# main3.net
KiCad netlist of a schematic drawn in EAGLE
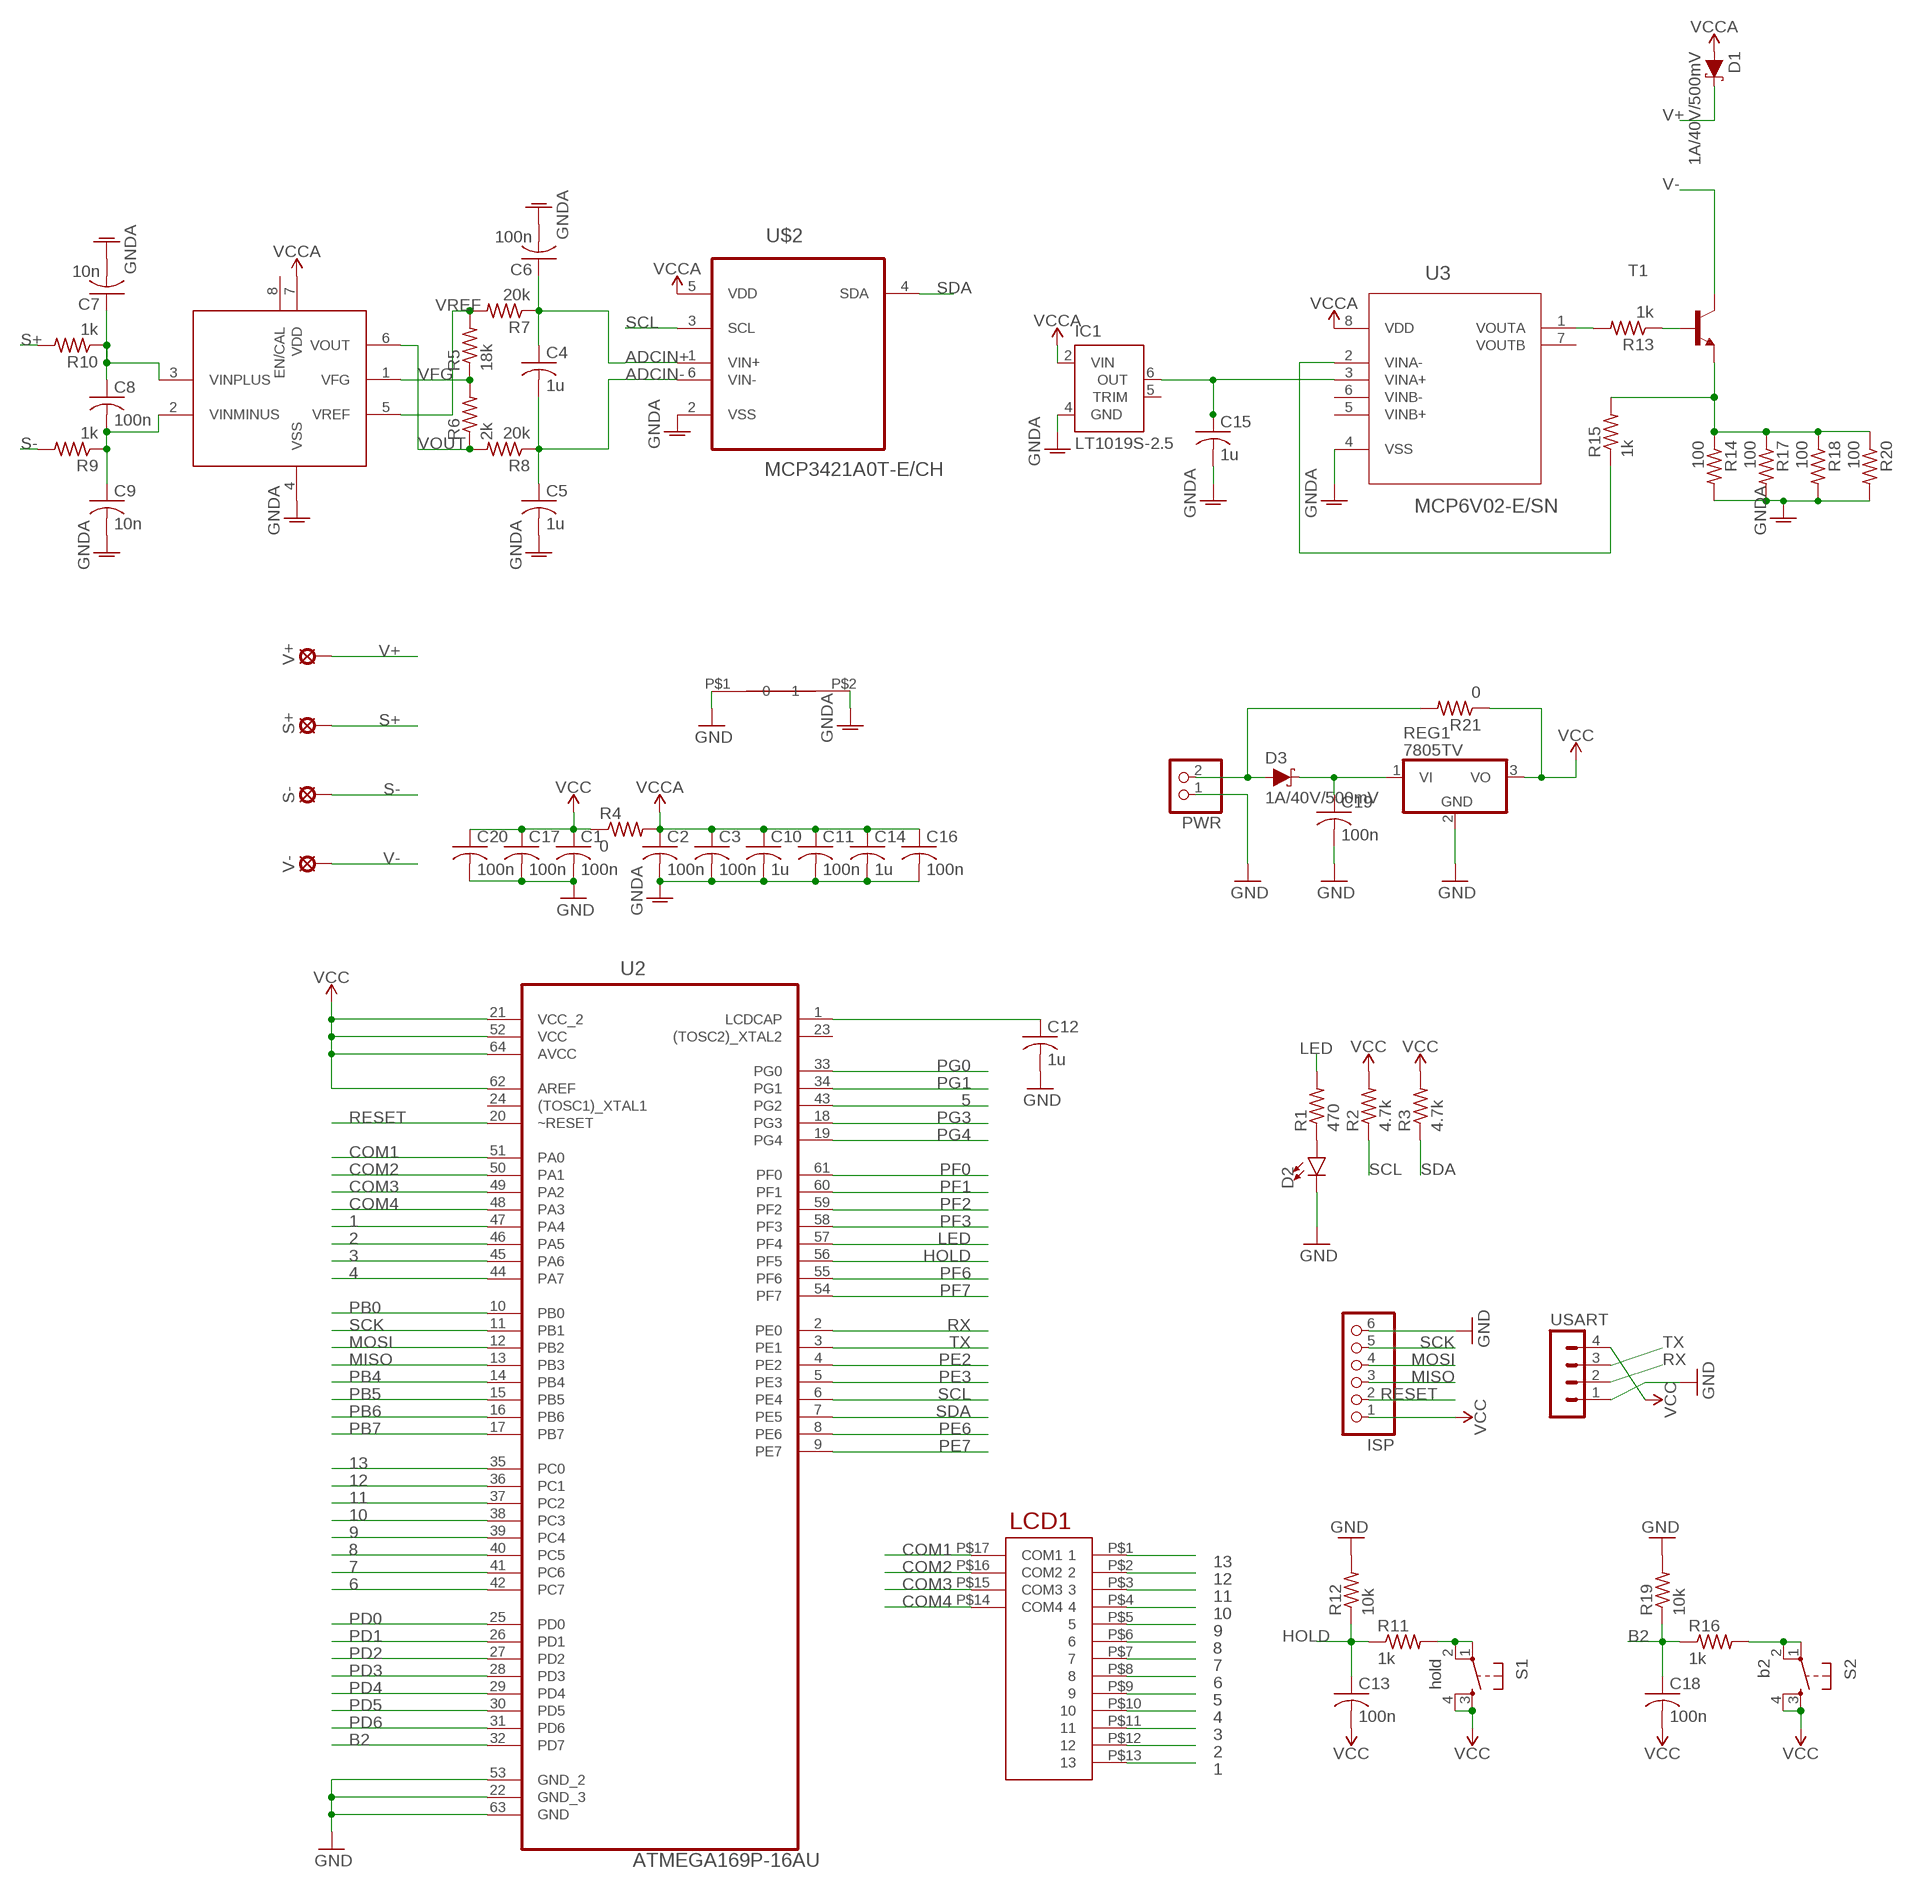
[diagram p0: schematic, sheet 1]

(export (version "E")
  (design (tool "Eeschema 10.0.6"))
  (components
    (comp (ref "C1")
      (value "100n")
      (footprint "eagle-import:C0603")
      (libsource (lib "eagle-import") (part "C-USC0603"))
    )
    (comp (ref "C2")
      (value "100n")
      (footprint "eagle-import:C0603")
      (libsource (lib "eagle-import") (part "C-USC0603"))
    )
    (comp (ref "C3")
      (value "100n")
      (footprint "eagle-import:C0603")
      (libsource (lib "eagle-import") (part "C-USC0603"))
    )
    (comp (ref "C4")
      (value "1u")
      (footprint "eagle-import:C0603")
      (libsource (lib "eagle-import") (part "C-USC0603"))
    )
    (comp (ref "C5")
      (value "1u")
      (footprint "eagle-import:C0603")
      (libsource (lib "eagle-import") (part "C-USC0603"))
    )
    (comp (ref "C6")
      (value "100n")
      (footprint "eagle-import:C0603")
      (libsource (lib "eagle-import") (part "C-USC0603"))
    )
    (comp (ref "C7")
      (value "10n")
      (footprint "eagle-import:C0603")
      (libsource (lib "eagle-import") (part "C-USC0603"))
    )
    (comp (ref "C8")
      (value "100n")
      (footprint "eagle-import:C0603")
      (libsource (lib "eagle-import") (part "C-USC0603"))
    )
    (comp (ref "C9")
      (value "10n")
      (footprint "eagle-import:C0603")
      (libsource (lib "eagle-import") (part "C-USC0603"))
    )
    (comp (ref "C10")
      (value "1u")
      (footprint "eagle-import:C0603")
      (libsource (lib "eagle-import") (part "C-USC0603"))
    )
    (comp (ref "C11")
      (value "100n")
      (footprint "eagle-import:C0603")
      (libsource (lib "eagle-import") (part "C-USC0603"))
    )
    (comp (ref "C12")
      (value "1u")
      (footprint "eagle-import:C0603")
      (libsource (lib "eagle-import") (part "C-USC0603"))
    )
    (comp (ref "C13")
      (value "100n")
      (footprint "eagle-import:C0603")
      (libsource (lib "eagle-import") (part "C-USC0603"))
    )
    (comp (ref "C14")
      (value "1u")
      (footprint "eagle-import:C0603")
      (libsource (lib "eagle-import") (part "C-USC0603"))
    )
    (comp (ref "C15")
      (value "1u")
      (footprint "eagle-import:C0603")
      (libsource (lib "eagle-import") (part "C-USC0603"))
    )
    (comp (ref "C16")
      (value "100n")
      (footprint "eagle-import:C0603")
      (libsource (lib "eagle-import") (part "C-USC0603"))
    )
    (comp (ref "C17")
      (value "100n")
      (footprint "eagle-import:C0603")
      (libsource (lib "eagle-import") (part "C-USC0603"))
    )
    (comp (ref "C18")
      (value "100n")
      (footprint "eagle-import:C0603")
      (libsource (lib "eagle-import") (part "C-USC0603"))
    )
    (comp (ref "C19")
      (value "100n")
      (footprint "eagle-import:C0603")
      (libsource (lib "eagle-import") (part "C-USC0603"))
    )
    (comp (ref "C20")
      (value "100n")
      (footprint "eagle-import:C0603")
      (libsource (lib "eagle-import") (part "C-USC0603"))
    )
    (comp (ref "D1")
      (value "1A/40V/500mV")
      (footprint "eagle-import:SMA-DIODE")
      (libsource (lib "eagle-import") (part "DIODE-SCHOTTKY-SS14"))
    )
    (comp (ref "D2")
      (value "LED5MM")
      (footprint "eagle-import:LED_5MM")
      (libsource (lib "eagle-import") (part "LED5MM"))
    )
    (comp (ref "D3")
      (value "1A/40V/500mV")
      (footprint "eagle-import:SMA-DIODE")
      (libsource (lib "eagle-import") (part "DIODE-SCHOTTKY-SS14"))
    )
    (comp (ref "IC1")
      (value "LT1019S-2.5")
      (footprint "eagle-import:SOIC8")
      (fields (field (name "MPN") "LT1019CS8-2.5#PBF"))
      (libsource (lib "eagle-import") (part "LT1019?S-2.5"))
    )
    (comp (ref "ISP")
      (value "PINHD-1X6")
      (footprint "eagle-import:1X06")
      (libsource (lib "eagle-import") (part "PINHD-1X6"))
    )
    (comp (ref "LCD1")
      (value "GDC0570_LCD")
      (footprint "eagle-import:GDC0570_LCD")
      (libsource (lib "eagle-import") (part "GDC0570_LCD"))
    )
    (comp (ref "PWR")
      (value "PINHD-1X2")
      (footprint "eagle-import:1X02")
      (libsource (lib "eagle-import") (part "PINHD-1X2"))
    )
    (comp (ref "R1")
      (value "470")
      (footprint "eagle-import:R0603")
      (libsource (lib "eagle-import") (part "R-US_R0603"))
    )
    (comp (ref "R2")
      (value "4.7k")
      (footprint "eagle-import:R0603")
      (libsource (lib "eagle-import") (part "R-US_R0603"))
    )
    (comp (ref "R3")
      (value "4.7k")
      (footprint "eagle-import:R0603")
      (libsource (lib "eagle-import") (part "R-US_R0603"))
    )
    (comp (ref "R4")
      (value "0")
      (footprint "eagle-import:0309_12")
      (libsource (lib "eagle-import") (part "R-US_0309/12"))
    )
    (comp (ref "R5")
      (value "18k")
      (footprint "eagle-import:R0603")
      (libsource (lib "eagle-import") (part "R-US_R0603"))
    )
    (comp (ref "R6")
      (value "2k")
      (footprint "eagle-import:R0603")
      (libsource (lib "eagle-import") (part "R-US_R0603"))
    )
    (comp (ref "R7")
      (value "20k")
      (footprint "eagle-import:R0603")
      (libsource (lib "eagle-import") (part "R-US_R0603"))
    )
    (comp (ref "R8")
      (value "20k")
      (footprint "eagle-import:R0603")
      (libsource (lib "eagle-import") (part "R-US_R0603"))
    )
    (comp (ref "R9")
      (value "1k")
      (footprint "eagle-import:R0603")
      (libsource (lib "eagle-import") (part "R-US_R0603"))
    )
    (comp (ref "R10")
      (value "1k")
      (footprint "eagle-import:R0603")
      (libsource (lib "eagle-import") (part "R-US_R0603"))
    )
    (comp (ref "R11")
      (value "1k")
      (footprint "eagle-import:R0603")
      (libsource (lib "eagle-import") (part "R-US_R0603"))
    )
    (comp (ref "R12")
      (value "10k")
      (footprint "eagle-import:R0603")
      (libsource (lib "eagle-import") (part "R-US_R0603"))
    )
    (comp (ref "R13")
      (value "1k")
      (footprint "eagle-import:R0603")
      (libsource (lib "eagle-import") (part "R-US_R0603"))
    )
    (comp (ref "R14")
      (value "100")
      (footprint "eagle-import:R0603")
      (libsource (lib "eagle-import") (part "R-US_R0603"))
    )
    (comp (ref "R15")
      (value "1k")
      (footprint "eagle-import:R0603")
      (libsource (lib "eagle-import") (part "R-US_R0603"))
    )
    (comp (ref "R16")
      (value "1k")
      (footprint "eagle-import:R0603")
      (libsource (lib "eagle-import") (part "R-US_R0603"))
    )
    (comp (ref "R17")
      (value "100")
      (footprint "eagle-import:R0603")
      (libsource (lib "eagle-import") (part "R-US_R0603"))
    )
    (comp (ref "R18")
      (value "100")
      (footprint "eagle-import:R0603")
      (libsource (lib "eagle-import") (part "R-US_R0603"))
    )
    (comp (ref "R19")
      (value "10k")
      (footprint "eagle-import:R0603")
      (libsource (lib "eagle-import") (part "R-US_R0603"))
    )
    (comp (ref "R20")
      (value "100")
      (footprint "eagle-import:R0603")
      (libsource (lib "eagle-import") (part "R-US_R0603"))
    )
    (comp (ref "R21")
      (value "0")
      (footprint "eagle-import:R0603")
      (libsource (lib "eagle-import") (part "R-US_R0603"))
    )
    (comp (ref "REG1")
      (value "7805TV")
      (footprint "eagle-import:TO220V")
      (libsource (lib "eagle-import") (part "78TV05"))
    )
    (comp (ref "S+")
      (value "MCS08")
      (footprint "eagle-import:MCS08")
      (libsource (lib "eagle-import") (part "MCS08"))
    )
    (comp (ref "S-")
      (value "MCS08")
      (footprint "eagle-import:MCS08")
      (libsource (lib "eagle-import") (part "MCS08"))
    )
    (comp (ref "S1")
      (value "hold")
      (footprint "eagle-import:TACTILE-PTH")
      (libsource (lib "eagle-import") (part "TAC_SWITCHPTH"))
    )
    (comp (ref "S2")
      (value "b2")
      (footprint "eagle-import:TACTILE-PTH")
      (libsource (lib "eagle-import") (part "TAC_SWITCHPTH"))
    )
    (comp (ref "T1")
      (value "MMBT3904LT1-NPN-SOT23-BEC")
      (footprint "eagle-import:SOT23-BEC")
      (libsource (lib "eagle-import") (part "-NPN-SOT23-BECMMBT3904LT1"))
    )
    (comp (ref "U$2")
      (value "MCP3421A0T-E/CH")
      (footprint "eagle-import:SOT95P270X145-6N")
      (libsource (lib "eagle-import") (part "MCP3421A0T-E/CH"))
    )
    (comp (ref "U$3")
      (value "MCP6N11")
      (footprint "eagle-import:SOIC8")
      (libsource (lib "eagle-import") (part "MCP6N11"))
    )
    (comp (ref "U$10")
      (value "SHORT32")
      (footprint "eagle-import:SHORT_32")
      (libsource (lib "eagle-import") (part "SHORT32"))
    )
    (comp (ref "U2")
      (value "ATMEGA169P-16AU")
      (footprint "eagle-import:QFP80P1600X1600X120-64N")
      (libsource (lib "eagle-import") (part "ATMEGA169P-16AU"))
    )
    (comp (ref "U3")
      (value "MCP6V02-E/SN")
      (footprint "eagle-import:SOIC127P600X175-8N")
      (libsource (lib "eagle-import") (part "MCP6V02-E/SN"))
    )
    (comp (ref "USART")
      (value "MA04-1")
      (footprint "eagle-import:MA04-1")
      (libsource (lib "eagle-import") (part "MA04-1"))
    )
    (comp (ref "V+")
      (value "MCS08")
      (footprint "eagle-import:MCS08")
      (libsource (lib "eagle-import") (part "MCS08"))
    )
    (comp (ref "V-")
      (value "MCS08")
      (footprint "eagle-import:MCS08")
      (libsource (lib "eagle-import") (part "MCS08"))
    )
  )
  (nets
    (net (code "1") (name "/1") (class "Default")
      (node (ref "LCD1") (pin "P$13") (pinfunction "13_P$13") (pintype "bidirectional"))
      (node (ref "U2") (pin "47") (pinfunction "PA4_47") (pintype "bidirectional"))
    )
    (net (code "2") (name "/2") (class "Default")
      (node (ref "LCD1") (pin "P$12") (pinfunction "12_P$12") (pintype "bidirectional"))
      (node (ref "U2") (pin "46") (pinfunction "PA5_46") (pintype "bidirectional"))
    )
    (net (code "3") (name "/3") (class "Default")
      (node (ref "LCD1") (pin "P$11") (pinfunction "11_P$11") (pintype "bidirectional"))
      (node (ref "U2") (pin "45") (pinfunction "PA6_45") (pintype "bidirectional"))
    )
    (net (code "4") (name "/4") (class "Default")
      (node (ref "LCD1") (pin "P$10") (pinfunction "10_P$10") (pintype "bidirectional"))
      (node (ref "U2") (pin "44") (pinfunction "PA7_44") (pintype "bidirectional"))
    )
    (net (code "5") (name "/5") (class "Default")
      (node (ref "LCD1") (pin "P$9") (pinfunction "9_P$9") (pintype "bidirectional"))
      (node (ref "U2") (pin "43") (pinfunction "PG2_43") (pintype "bidirectional"))
    )
    (net (code "6") (name "/6") (class "Default")
      (node (ref "LCD1") (pin "P$8") (pinfunction "8_P$8") (pintype "bidirectional"))
      (node (ref "U2") (pin "42") (pinfunction "PC7_42") (pintype "bidirectional"))
    )
    (net (code "7") (name "/7") (class "Default")
      (node (ref "LCD1") (pin "P$7") (pinfunction "7_P$7") (pintype "bidirectional"))
      (node (ref "U2") (pin "41") (pinfunction "PC6_41") (pintype "bidirectional"))
    )
    (net (code "8") (name "/8") (class "Default")
      (node (ref "LCD1") (pin "P$6") (pinfunction "6_P$6") (pintype "bidirectional"))
      (node (ref "U2") (pin "40") (pinfunction "PC5_40") (pintype "bidirectional"))
    )
    (net (code "9") (name "/9") (class "Default")
      (node (ref "LCD1") (pin "P$5") (pinfunction "5_P$5") (pintype "bidirectional"))
      (node (ref "U2") (pin "39") (pinfunction "PC4_39") (pintype "bidirectional"))
    )
    (net (code "10") (name "/10") (class "Default")
      (node (ref "LCD1") (pin "P$4") (pinfunction "4_P$4") (pintype "bidirectional"))
      (node (ref "U2") (pin "38") (pinfunction "PC3_38") (pintype "bidirectional"))
    )
    (net (code "11") (name "/11") (class "Default")
      (node (ref "LCD1") (pin "P$3") (pinfunction "3_P$3") (pintype "bidirectional"))
      (node (ref "U2") (pin "37") (pinfunction "PC2_37") (pintype "bidirectional"))
    )
    (net (code "12") (name "/12") (class "Default")
      (node (ref "LCD1") (pin "P$2") (pinfunction "2_P$2") (pintype "bidirectional"))
      (node (ref "U2") (pin "36") (pinfunction "PC1_36") (pintype "bidirectional"))
    )
    (net (code "13") (name "/13") (class "Default")
      (node (ref "LCD1") (pin "P$1") (pinfunction "1_P$1") (pintype "bidirectional"))
      (node (ref "U2") (pin "35") (pinfunction "PC0_35") (pintype "bidirectional"))
    )
    (net (code "14") (name "/ADCIN+") (class "Default")
      (node (ref "C4") (pin "1") (pinfunction "1_1") (pintype "passive"))
      (node (ref "C6") (pin "1") (pinfunction "1_1") (pintype "passive"))
      (node (ref "R7") (pin "1") (pinfunction "1_1") (pintype "passive"))
      (node (ref "U$2") (pin "1") (pinfunction "VIN+_1") (pintype "input"))
    )
    (net (code "15") (name "/ADCIN-") (class "Default")
      (node (ref "C4") (pin "2") (pinfunction "2_2") (pintype "passive"))
      (node (ref "C5") (pin "1") (pinfunction "1_1") (pintype "passive"))
      (node (ref "R8") (pin "1") (pinfunction "1_1") (pintype "passive"))
      (node (ref "U$2") (pin "6") (pinfunction "VIN-_6") (pintype "input"))
    )
    (net (code "16") (name "/B2") (class "Default")
      (node (ref "C18") (pin "1") (pinfunction "1_1") (pintype "passive"))
      (node (ref "R16") (pin "1") (pinfunction "1_1") (pintype "passive"))
      (node (ref "R19") (pin "1") (pinfunction "1_1") (pintype "passive"))
      (node (ref "U2") (pin "32") (pinfunction "PD7_32") (pintype "bidirectional"))
    )
    (net (code "17") (name "/COM1") (class "Default")
      (node (ref "LCD1") (pin "P$17") (pinfunction "COM1_P$17") (pintype "bidirectional"))
      (node (ref "U2") (pin "51") (pinfunction "PA0_51") (pintype "bidirectional"))
    )
    (net (code "18") (name "/COM2") (class "Default")
      (node (ref "LCD1") (pin "P$16") (pinfunction "COM2_P$16") (pintype "bidirectional"))
      (node (ref "U2") (pin "50") (pinfunction "PA1_50") (pintype "bidirectional"))
    )
    (net (code "19") (name "/COM3") (class "Default")
      (node (ref "LCD1") (pin "P$15") (pinfunction "COM3_P$15") (pintype "bidirectional"))
      (node (ref "U2") (pin "49") (pinfunction "PA2_49") (pintype "bidirectional"))
    )
    (net (code "20") (name "/COM4") (class "Default")
      (node (ref "LCD1") (pin "P$14") (pinfunction "COM4_P$14") (pintype "bidirectional"))
      (node (ref "U2") (pin "48") (pinfunction "PA3_48") (pintype "bidirectional"))
    )
    (net (code "21") (name "/HOLD") (class "Default")
      (node (ref "C13") (pin "1") (pinfunction "1_1") (pintype "passive"))
      (node (ref "R11") (pin "1") (pinfunction "1_1") (pintype "passive"))
      (node (ref "R12") (pin "1") (pinfunction "1_1") (pintype "passive"))
      (node (ref "U2") (pin "56") (pinfunction "PF5_56") (pintype "bidirectional"))
    )
    (net (code "22") (name "/LED") (class "Default")
      (node (ref "R1") (pin "2") (pinfunction "2_2") (pintype "passive"))
      (node (ref "U2") (pin "57") (pinfunction "PF4_57") (pintype "bidirectional"))
    )
    (net (code "23") (name "/MISO") (class "Default")
      (node (ref "ISP") (pin "3") (pinfunction "3_3") (pintype "passive"))
      (node (ref "U2") (pin "13") (pinfunction "PB3_13") (pintype "bidirectional"))
    )
    (net (code "24") (name "/MOSI") (class "Default")
      (node (ref "ISP") (pin "4") (pinfunction "4_4") (pintype "passive"))
      (node (ref "U2") (pin "12") (pinfunction "PB2_12") (pintype "bidirectional"))
    )
    (net (code "25") (name "/PB0") (class "Default")
      (node (ref "U2") (pin "10") (pinfunction "PB0_10") (pintype "bidirectional"))
    )
    (net (code "26") (name "/PB4") (class "Default")
      (node (ref "U2") (pin "14") (pinfunction "PB4_14") (pintype "bidirectional"))
    )
    (net (code "27") (name "/PB5") (class "Default")
      (node (ref "U2") (pin "15") (pinfunction "PB5_15") (pintype "bidirectional"))
    )
    (net (code "28") (name "/PB6") (class "Default")
      (node (ref "U2") (pin "16") (pinfunction "PB6_16") (pintype "bidirectional"))
    )
    (net (code "29") (name "/PB7") (class "Default")
      (node (ref "U2") (pin "17") (pinfunction "PB7_17") (pintype "bidirectional"))
    )
    (net (code "30") (name "/PD0") (class "Default")
      (node (ref "U2") (pin "25") (pinfunction "PD0_25") (pintype "bidirectional"))
    )
    (net (code "31") (name "/PD1") (class "Default")
      (node (ref "U2") (pin "26") (pinfunction "PD1_26") (pintype "bidirectional"))
    )
    (net (code "32") (name "/PD2") (class "Default")
      (node (ref "U2") (pin "27") (pinfunction "PD2_27") (pintype "bidirectional"))
    )
    (net (code "33") (name "/PD3") (class "Default")
      (node (ref "U2") (pin "28") (pinfunction "PD3_28") (pintype "bidirectional"))
    )
    (net (code "34") (name "/PD4") (class "Default")
      (node (ref "U2") (pin "29") (pinfunction "PD4_29") (pintype "bidirectional"))
    )
    (net (code "35") (name "/PD5") (class "Default")
      (node (ref "U2") (pin "30") (pinfunction "PD5_30") (pintype "bidirectional"))
    )
    (net (code "36") (name "/PD6") (class "Default")
      (node (ref "U2") (pin "31") (pinfunction "PD6_31") (pintype "bidirectional"))
    )
    (net (code "37") (name "/PE2") (class "Default")
      (node (ref "U2") (pin "4") (pinfunction "PE2_4") (pintype "bidirectional"))
    )
    (net (code "38") (name "/PE3") (class "Default")
      (node (ref "U2") (pin "5") (pinfunction "PE3_5") (pintype "bidirectional"))
    )
    (net (code "39") (name "/PE6") (class "Default")
      (node (ref "U2") (pin "8") (pinfunction "PE6_8") (pintype "bidirectional"))
    )
    (net (code "40") (name "/PE7") (class "Default")
      (node (ref "U2") (pin "9") (pinfunction "PE7_9") (pintype "bidirectional"))
    )
    (net (code "41") (name "/PF0") (class "Default")
      (node (ref "U2") (pin "61") (pinfunction "PF0_61") (pintype "bidirectional"))
    )
    (net (code "42") (name "/PF1") (class "Default")
      (node (ref "U2") (pin "60") (pinfunction "PF1_60") (pintype "bidirectional"))
    )
    (net (code "43") (name "/PF2") (class "Default")
      (node (ref "U2") (pin "59") (pinfunction "PF2_59") (pintype "bidirectional"))
    )
    (net (code "44") (name "/PF3") (class "Default")
      (node (ref "U2") (pin "58") (pinfunction "PF3_58") (pintype "bidirectional"))
    )
    (net (code "45") (name "/PF6") (class "Default")
      (node (ref "U2") (pin "55") (pinfunction "PF6_55") (pintype "bidirectional"))
    )
    (net (code "46") (name "/PF7") (class "Default")
      (node (ref "U2") (pin "54") (pinfunction "PF7_54") (pintype "bidirectional"))
    )
    (net (code "47") (name "/PG0") (class "Default")
      (node (ref "U2") (pin "33") (pinfunction "PG0_33") (pintype "bidirectional"))
    )
    (net (code "48") (name "/PG1") (class "Default")
      (node (ref "U2") (pin "34") (pinfunction "PG1_34") (pintype "bidirectional"))
    )
    (net (code "49") (name "/PG3") (class "Default")
      (node (ref "U2") (pin "18") (pinfunction "PG3_18") (pintype "bidirectional"))
    )
    (net (code "50") (name "/PG4") (class "Default")
      (node (ref "U2") (pin "19") (pinfunction "PG4_19") (pintype "bidirectional"))
    )
    (net (code "51") (name "/RESET") (class "Default")
      (node (ref "ISP") (pin "2") (pinfunction "2_2") (pintype "passive"))
      (node (ref "U2") (pin "20") (pinfunction "~{RESET}_20") (pintype "input"))
    )
    (net (code "52") (name "/RX") (class "Default")
      (node (ref "U2") (pin "2") (pinfunction "PE0_2") (pintype "bidirectional"))
      (node (ref "USART") (pin "2") (pinfunction "2_2") (pintype "passive"))
    )
    (net (code "53") (name "/S+") (class "Default")
      (node (ref "R10") (pin "2") (pinfunction "2_2") (pintype "passive"))
      (node (ref "S+") (pin "MP") (pinfunction "MP_MP") (pintype "passive"))
    )
    (net (code "54") (name "/S-") (class "Default")
      (node (ref "R9") (pin "2") (pinfunction "2_2") (pintype "passive"))
      (node (ref "S-") (pin "MP") (pinfunction "MP_MP") (pintype "passive"))
    )
    (net (code "55") (name "/SCK") (class "Default")
      (node (ref "ISP") (pin "5") (pinfunction "5_5") (pintype "passive"))
      (node (ref "U2") (pin "11") (pinfunction "PB1_11") (pintype "bidirectional"))
    )
    (net (code "56") (name "/SCL") (class "Default")
      (node (ref "R2") (pin "1") (pinfunction "1_1") (pintype "passive"))
      (node (ref "U$2") (pin "3") (pinfunction "SCL_3") (pintype "input"))
      (node (ref "U2") (pin "6") (pinfunction "PE4_6") (pintype "bidirectional"))
    )
    (net (code "57") (name "/SDA") (class "Default")
      (node (ref "R3") (pin "1") (pinfunction "1_1") (pintype "passive"))
      (node (ref "U$2") (pin "4") (pinfunction "SDA_4") (pintype "bidirectional"))
      (node (ref "U2") (pin "7") (pinfunction "PE5_7") (pintype "bidirectional"))
    )
    (net (code "58") (name "/TX") (class "Default")
      (node (ref "U2") (pin "3") (pinfunction "PE1_3") (pintype "bidirectional"))
      (node (ref "USART") (pin "3") (pinfunction "3_3") (pintype "passive"))
    )
    (net (code "59") (name "/V+") (class "Default")
      (node (ref "D1") (pin "C") (pinfunction "C_C") (pintype "passive"))
      (node (ref "V+") (pin "MP") (pinfunction "MP_MP") (pintype "passive"))
    )
    (net (code "60") (name "/V-") (class "Default")
      (node (ref "T1") (pin "C") (pinfunction "C_C") (pintype "passive"))
      (node (ref "V-") (pin "MP") (pinfunction "MP_MP") (pintype "passive"))
    )
    (net (code "61") (name "/VFG") (class "Default")
      (node (ref "R5") (pin "1") (pinfunction "1_1") (pintype "passive"))
      (node (ref "R6") (pin "2") (pinfunction "2_2") (pintype "passive"))
      (node (ref "U$3") (pin "1") (pinfunction "VFG_1") (pintype "bidirectional"))
    )
    (net (code "62") (name "/VOUT") (class "Default")
      (node (ref "R6") (pin "1") (pinfunction "1_1") (pintype "passive"))
      (node (ref "R8") (pin "2") (pinfunction "2_2") (pintype "passive"))
      (node (ref "U$3") (pin "6") (pinfunction "VOUT_6") (pintype "bidirectional"))
    )
    (net (code "63") (name "/VREF") (class "Default")
      (node (ref "R5") (pin "2") (pinfunction "2_2") (pintype "passive"))
      (node (ref "R7") (pin "2") (pinfunction "2_2") (pintype "passive"))
      (node (ref "U$3") (pin "5") (pinfunction "VREF_5") (pintype "bidirectional"))
    )
    (net (code "64") (name "GND") (class "Default")
      (node (ref "C1") (pin "2") (pinfunction "2_2") (pintype "passive"))
      (node (ref "C12") (pin "2") (pinfunction "2_2") (pintype "passive"))
      (node (ref "C17") (pin "2") (pinfunction "2_2") (pintype "passive"))
      (node (ref "C19") (pin "2") (pinfunction "2_2") (pintype "passive"))
      (node (ref "C20") (pin "2") (pinfunction "2_2") (pintype "passive"))
      (node (ref "D2") (pin "K") (pinfunction "C_K") (pintype "passive"))
      (node (ref "ISP") (pin "6") (pinfunction "6_6") (pintype "passive"))
      (node (ref "PWR") (pin "1") (pinfunction "1_1") (pintype "passive"))
      (node (ref "R12") (pin "2") (pinfunction "2_2") (pintype "passive"))
      (node (ref "R19") (pin "2") (pinfunction "2_2") (pintype "passive"))
      (node (ref "REG1") (pin "2") (pinfunction "GND_2") (pintype "passive"))
      (node (ref "U$10") (pin "P$1") (pinfunction "0_P$1") (pintype "bidirectional"))
      (node (ref "U2") (pin "22") (pinfunction "GND_3_22") (pintype "passive"))
      (node (ref "U2") (pin "53") (pinfunction "GND_2_53") (pintype "passive"))
      (node (ref "U2") (pin "63") (pinfunction "GND_63") (pintype "passive"))
      (node (ref "USART") (pin "1") (pinfunction "1_1") (pintype "passive"))
    )
    (net (code "65") (name "GNDA") (class "Default")
      (node (ref "C10") (pin "2") (pinfunction "2_2") (pintype "passive"))
      (node (ref "C11") (pin "2") (pinfunction "2_2") (pintype "passive"))
      (node (ref "C14") (pin "2") (pinfunction "2_2") (pintype "passive"))
      (node (ref "C15") (pin "2") (pinfunction "2_2") (pintype "passive"))
      (node (ref "C16") (pin "2") (pinfunction "2_2") (pintype "passive"))
      (node (ref "C2") (pin "2") (pinfunction "2_2") (pintype "passive"))
      (node (ref "C3") (pin "2") (pinfunction "2_2") (pintype "passive"))
      (node (ref "C5") (pin "2") (pinfunction "2_2") (pintype "passive"))
      (node (ref "C6") (pin "2") (pinfunction "2_2") (pintype "passive"))
      (node (ref "C7") (pin "2") (pinfunction "2_2") (pintype "passive"))
      (node (ref "C9") (pin "2") (pinfunction "2_2") (pintype "passive"))
      (node (ref "IC1") (pin "4") (pinfunction "GND_4") (pintype "power_in"))
      (node (ref "R14") (pin "2") (pinfunction "2_2") (pintype "passive"))
      (node (ref "R17") (pin "2") (pinfunction "2_2") (pintype "passive"))
      (node (ref "R18") (pin "2") (pinfunction "2_2") (pintype "passive"))
      (node (ref "R20") (pin "2") (pinfunction "2_2") (pintype "passive"))
      (node (ref "U$10") (pin "P$2") (pinfunction "1_P$2") (pintype "bidirectional"))
      (node (ref "U$2") (pin "2") (pinfunction "VSS_2") (pintype "passive"))
      (node (ref "U$3") (pin "4") (pinfunction "VSS_4") (pintype "bidirectional"))
      (node (ref "U3") (pin "4") (pinfunction "VSS_4") (pintype "power_in"))
    )
    (net (code "66") (name "Net-(D2-PadA)") (class "Default")
      (node (ref "D2") (pin "A") (pinfunction "A_A") (pintype "passive"))
      (node (ref "R1") (pin "1") (pinfunction "1_1") (pintype "passive"))
    )
    (net (code "67") (name "Net-(D3-PadA)") (class "Default")
      (node (ref "D3") (pin "A") (pinfunction "A_A") (pintype "passive"))
      (node (ref "PWR") (pin "2") (pinfunction "2_2") (pintype "passive"))
      (node (ref "R21") (pin "2") (pinfunction "2_2") (pintype "passive"))
    )
    (net (code "68") (name "Net-(IC1-OUT)") (class "Default")
      (node (ref "C15") (pin "1") (pinfunction "1_1") (pintype "passive"))
      (node (ref "IC1") (pin "6") (pinfunction "OUT_6") (pintype "input"))
      (node (ref "U3") (pin "3") (pinfunction "VINA+_3") (pintype "input"))
    )
    (net (code "69") (name "Net-(R11-Pad2)") (class "Default")
      (node (ref "R11") (pin "2") (pinfunction "2_2") (pintype "passive"))
      (node (ref "S1") (pin "1") (pinfunction "1_1") (pintype "passive"))
      (node (ref "S1") (pin "2") (pinfunction "2_2") (pintype "passive"))
    )
    (net (code "70") (name "Net-(R13-Pad1)") (class "Default")
      (node (ref "R13") (pin "1") (pinfunction "1_1") (pintype "passive"))
      (node (ref "T1") (pin "B") (pinfunction "B_B") (pintype "passive"))
    )
    (net (code "71") (name "Net-(R14-Pad1)") (class "Default")
      (node (ref "R14") (pin "1") (pinfunction "1_1") (pintype "passive"))
      (node (ref "R15") (pin "2") (pinfunction "2_2") (pintype "passive"))
      (node (ref "R17") (pin "1") (pinfunction "1_1") (pintype "passive"))
      (node (ref "R18") (pin "1") (pinfunction "1_1") (pintype "passive"))
      (node (ref "R20") (pin "1") (pinfunction "1_1") (pintype "passive"))
      (node (ref "T1") (pin "E") (pinfunction "E_E") (pintype "passive"))
    )
    (net (code "72") (name "Net-(R16-Pad2)") (class "Default")
      (node (ref "R16") (pin "2") (pinfunction "2_2") (pintype "passive"))
      (node (ref "S2") (pin "1") (pinfunction "1_1") (pintype "passive"))
      (node (ref "S2") (pin "2") (pinfunction "2_2") (pintype "passive"))
    )
    (net (code "73") (name "Net-(REG1-VI)") (class "Default")
      (node (ref "C19") (pin "1") (pinfunction "1_1") (pintype "passive"))
      (node (ref "D3") (pin "C") (pinfunction "C_C") (pintype "passive"))
      (node (ref "REG1") (pin "1") (pinfunction "VI_1") (pintype "input"))
    )
    (net (code "74") (name "Net-(U$3-VINMINUS)") (class "Default")
      (node (ref "C8") (pin "2") (pinfunction "2_2") (pintype "passive"))
      (node (ref "C9") (pin "1") (pinfunction "1_1") (pintype "passive"))
      (node (ref "R9") (pin "1") (pinfunction "1_1") (pintype "passive"))
      (node (ref "U$3") (pin "2") (pinfunction "VINMINUS_2") (pintype "bidirectional"))
    )
    (net (code "75") (name "Net-(U$3-VINPLUS)") (class "Default")
      (node (ref "C7") (pin "1") (pinfunction "1_1") (pintype "passive"))
      (node (ref "C8") (pin "1") (pinfunction "1_1") (pintype "passive"))
      (node (ref "R10") (pin "1") (pinfunction "1_1") (pintype "passive"))
      (node (ref "U$3") (pin "3") (pinfunction "VINPLUS_3") (pintype "bidirectional"))
    )
    (net (code "76") (name "Net-(U2-LCDCAP)") (class "Default")
      (node (ref "C12") (pin "1") (pinfunction "1_1") (pintype "passive"))
      (node (ref "U2") (pin "1") (pinfunction "LCDCAP_1") (pintype "passive"))
    )
    (net (code "77") (name "Net-(U3-VINA-)") (class "Default")
      (node (ref "R15") (pin "1") (pinfunction "1_1") (pintype "passive"))
      (node (ref "U3") (pin "2") (pinfunction "VINA-_2") (pintype "input"))
    )
    (net (code "78") (name "Net-(U3-VOUTA)") (class "Default")
      (node (ref "R13") (pin "2") (pinfunction "2_2") (pintype "passive"))
      (node (ref "U3") (pin "1") (pinfunction "VOUTA_1") (pintype "output"))
    )
    (net (code "79") (name "VCC") (class "Default")
      (node (ref "C1") (pin "1") (pinfunction "1_1") (pintype "passive"))
      (node (ref "C13") (pin "2") (pinfunction "2_2") (pintype "passive"))
      (node (ref "C17") (pin "1") (pinfunction "1_1") (pintype "passive"))
      (node (ref "C18") (pin "2") (pinfunction "2_2") (pintype "passive"))
      (node (ref "C20") (pin "1") (pinfunction "1_1") (pintype "passive"))
      (node (ref "ISP") (pin "1") (pinfunction "1_1") (pintype "passive"))
      (node (ref "R2") (pin "2") (pinfunction "2_2") (pintype "passive"))
      (node (ref "R21") (pin "1") (pinfunction "1_1") (pintype "passive"))
      (node (ref "R3") (pin "2") (pinfunction "2_2") (pintype "passive"))
      (node (ref "R4") (pin "1") (pinfunction "1_1") (pintype "passive"))
      (node (ref "REG1") (pin "3") (pinfunction "VO_3") (pintype "passive"))
      (node (ref "S1") (pin "3") (pinfunction "3_3") (pintype "passive"))
      (node (ref "S1") (pin "4") (pinfunction "4_4") (pintype "passive"))
      (node (ref "S2") (pin "3") (pinfunction "3_3") (pintype "passive"))
      (node (ref "S2") (pin "4") (pinfunction "4_4") (pintype "passive"))
      (node (ref "U2") (pin "21") (pinfunction "VCC_2_21") (pintype "power_in"))
      (node (ref "U2") (pin "52") (pinfunction "VCC_52") (pintype "power_in"))
      (node (ref "U2") (pin "62") (pinfunction "AREF_62") (pintype "input"))
      (node (ref "U2") (pin "64") (pinfunction "AVCC_64") (pintype "power_in"))
      (node (ref "USART") (pin "4") (pinfunction "4_4") (pintype "passive"))
    )
    (net (code "80") (name "VCCA") (class "Default")
      (node (ref "C10") (pin "1") (pinfunction "1_1") (pintype "passive"))
      (node (ref "C11") (pin "1") (pinfunction "1_1") (pintype "passive"))
      (node (ref "C14") (pin "1") (pinfunction "1_1") (pintype "passive"))
      (node (ref "C16") (pin "1") (pinfunction "1_1") (pintype "passive"))
      (node (ref "C2") (pin "1") (pinfunction "1_1") (pintype "passive"))
      (node (ref "C3") (pin "1") (pinfunction "1_1") (pintype "passive"))
      (node (ref "D1") (pin "A") (pinfunction "A_A") (pintype "passive"))
      (node (ref "IC1") (pin "2") (pinfunction "VIN_2") (pintype "input"))
      (node (ref "R4") (pin "2") (pinfunction "2_2") (pintype "passive"))
      (node (ref "U$2") (pin "5") (pinfunction "VDD_5") (pintype "power_in"))
      (node (ref "U$3") (pin "7") (pinfunction "VDD_7") (pintype "bidirectional"))
      (node (ref "U3") (pin "8") (pinfunction "VDD_8") (pintype "power_in"))
    )
    (net (code "81") (name "unconnected-(IC1-TRIM-Pad5)") (class "Default")
      (node (ref "IC1") (pin "5") (pinfunction "TRIM_5") (pintype "passive"))
    )
    (net (code "82") (name "unconnected-(U$3-EN{slash}CAL-Pad8)") (class "Default")
      (node (ref "U$3") (pin "8") (pinfunction "EN/CAL_8") (pintype "bidirectional"))
    )
    (net (code "83") (name "unconnected-(U2-(TOSC1)_XTAL1-Pad24)") (class "Default")
      (node (ref "U2") (pin "24") (pinfunction "(TOSC1)_XTAL1_24") (pintype "input"))
    )
    (net (code "84") (name "unconnected-(U2-(TOSC2)_XTAL2-Pad23)") (class "Default")
      (node (ref "U2") (pin "23") (pinfunction "(TOSC2)_XTAL2_23") (pintype "output"))
    )
    (net (code "85") (name "unconnected-(U3-VINB+-Pad5)") (class "Default")
      (node (ref "U3") (pin "5") (pinfunction "VINB+_5") (pintype "input"))
    )
    (net (code "86") (name "unconnected-(U3-VINB--Pad6)") (class "Default")
      (node (ref "U3") (pin "6") (pinfunction "VINB-_6") (pintype "input"))
    )
    (net (code "87") (name "unconnected-(U3-VOUTB-Pad7)") (class "Default")
      (node (ref "U3") (pin "7") (pinfunction "VOUTB_7") (pintype "output"))
    )
  )
)
